# PushButtonBlack.net
KiCad netlist of a schematic drawn in Altium Designer
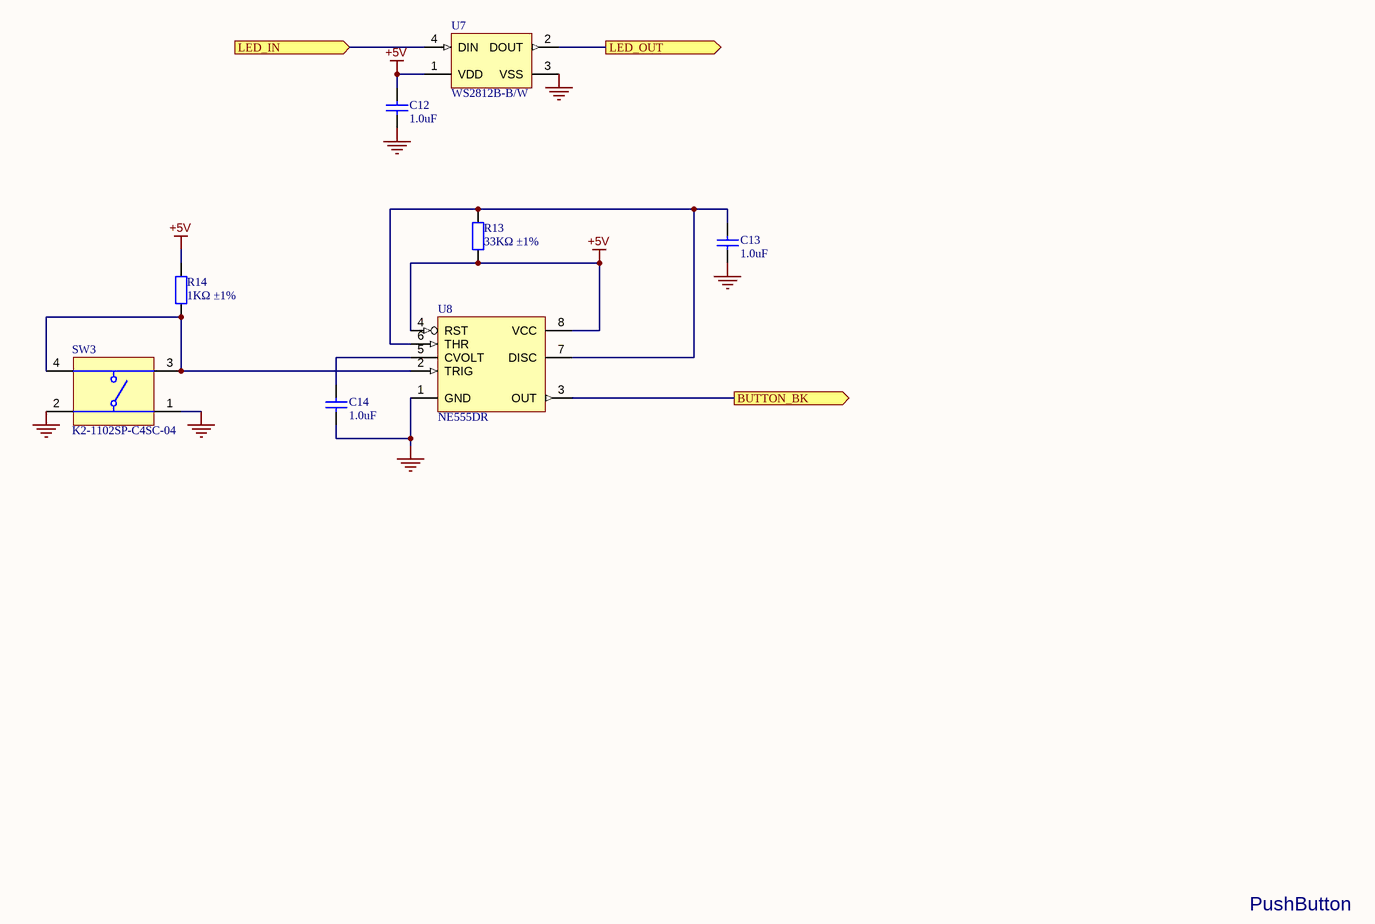
[diagram p0: PushButtonBlack.SchDoc]

(export (version "E")
  (design (tool "Eeschema 10.0.6"))
  (components
    (comp (ref "C12")
      (value "1.0uF")
      (footprint "0402_C")
      (description "Chip capacitor")
      (fields
        (field (name "MANUFACTURER") "Samsung Electro-Mechanics")
        (field (name "PARTNUMBER") "CL05A105KA5NQNC")
      )
      (libsource (lib "Cap") (part "0402 1.0uF (105) 10% 25V"))
    )
    (comp (ref "C13")
      (value "1.0uF")
      (footprint "0402_C")
      (description "Chip capacitor")
      (fields
        (field (name "MANUFACTURER") "Samsung Electro-Mechanics")
        (field (name "PARTNUMBER") "CL05A105KA5NQNC")
      )
      (libsource (lib "Cap") (part "0402 1.0uF (105) 10% 25V"))
    )
    (comp (ref "C14")
      (value "1.0uF")
      (footprint "0402_C")
      (description "Chip capacitor")
      (fields
        (field (name "MANUFACTURER") "Samsung Electro-Mechanics")
        (field (name "PARTNUMBER") "CL05A105KA5NQNC")
      )
      (libsource (lib "Cap") (part "0402 1.0uF (105) 10% 25V"))
    )
    (comp (ref "R13")
      (value "33KΩ ±1%")
      (footprint "0402_R")
      (description "Chip resistor")
      (fields (field (name "MANUFACTURER") "Uniroyal Elec") (field (name "PARTNUMBER") "0402WGF3302TCE"))
      (libsource (lib "RES") (part "0402 33K (3302) 1%"))
    )
    (comp (ref "R14")
      (value "1KΩ ±1%")
      (footprint "0402_R")
      (description "Chip resistor")
      (fields (field (name "MANUFACTURER") "Uniroyal Elec") (field (name "PARTNUMBER") "0402WGF1001TCE"))
      (libsource (lib "RES") (part "0402 1K (1001) 1%"))
    )
    (comp (ref "SW3")
      (value "K2-1102SP-C4SC-04")
      (footprint "TECO-FSM4JSMATR_V")
      (description "Top Actuated 50mA @ 12VDC Round Button SPST 6*6mm Tactile Switches ROHS")
      (libsource (lib "Altium Content Vault") (part "SW-SPST-4_A"))
    )
    (comp (ref "U7")
      (value "WS2812B-B/W")
      (footprint "ADA-RGB-1655_V")
      (fields (field (name "MANUFACTURER") "Worldsemi"))
      (libsource (lib "Altium Content Vault") (part "ADA-RGB-1655-4"))
    )
    (comp (ref "U8")
      (value "NE555DR")
      (footprint "SOIC-8_150mil")
      (description "时基集成")
      (libsource (lib "IC") (part "NE555DR_[C7593]"))
    )
  )
  (nets
    (net (code "1") (name "+5V") (class "Default")
      (node (ref "C12") (pin "2") (pinfunction "2_2") (pintype "passive"))
      (node (ref "R13") (pin "1") (pinfunction "1_1") (pintype "passive"))
      (node (ref "R14") (pin "1") (pinfunction "1_1") (pintype "passive"))
      (node (ref "U7") (pin "1") (pinfunction "VDD_1") (pintype "power_in"))
      (node (ref "U8") (pin "4") (pinfunction "RST_4") (pintype "input"))
      (node (ref "U8") (pin "8") (pinfunction "VCC_8") (pintype "power_in"))
    )
    (net (code "2") (name "/BUTTON_BK") (class "Default")
      (node (ref "U8") (pin "3") (pinfunction "OUT_3") (pintype "output"))
    )
    (net (code "3") (name "/LED_IN") (class "Default")
      (node (ref "U7") (pin "4") (pinfunction "DIN_4") (pintype "input"))
    )
    (net (code "4") (name "/LED_OUT") (class "Default")
      (node (ref "U7") (pin "2") (pinfunction "DOUT_2") (pintype "output"))
    )
    (net (code "5") (name "GND") (class "Default")
      (node (ref "C12") (pin "1") (pinfunction "1_1") (pintype "passive"))
      (node (ref "C13") (pin "1") (pinfunction "1_1") (pintype "passive"))
      (node (ref "C14") (pin "2") (pinfunction "2_2") (pintype "passive"))
      (node (ref "SW3") (pin "1") (pinfunction "1_1") (pintype "passive"))
      (node (ref "SW3") (pin "2") (pinfunction "2_2") (pintype "passive"))
      (node (ref "U7") (pin "3") (pinfunction "VSS_3") (pintype "power_in"))
      (node (ref "U8") (pin "1") (pinfunction "GND_1") (pintype "power_in"))
    )
    (net (code "6") (name "Net-(U8-CVOLT)") (class "Default")
      (node (ref "C14") (pin "1") (pinfunction "1_1") (pintype "passive"))
      (node (ref "U8") (pin "5") (pinfunction "CVOLT_5") (pintype "passive"))
    )
    (net (code "7") (name "Net-(U8-DISC)") (class "Default")
      (node (ref "C13") (pin "2") (pinfunction "2_2") (pintype "passive"))
      (node (ref "R13") (pin "2") (pinfunction "2_2") (pintype "passive"))
      (node (ref "U8") (pin "6") (pinfunction "THR_6") (pintype "input"))
      (node (ref "U8") (pin "7") (pinfunction "DISC_7") (pintype "open_collector"))
    )
    (net (code "8") (name "Net-(U8-TRIG)") (class "Default")
      (node (ref "R14") (pin "2") (pinfunction "2_2") (pintype "passive"))
      (node (ref "SW3") (pin "3") (pinfunction "3_3") (pintype "passive"))
      (node (ref "SW3") (pin "4") (pinfunction "4_4") (pintype "passive"))
      (node (ref "U8") (pin "2") (pinfunction "TRIG_2") (pintype "input"))
    )
  )
)
